# board_PMA.net
KiCad netlist of a schematic drawn in EAGLE
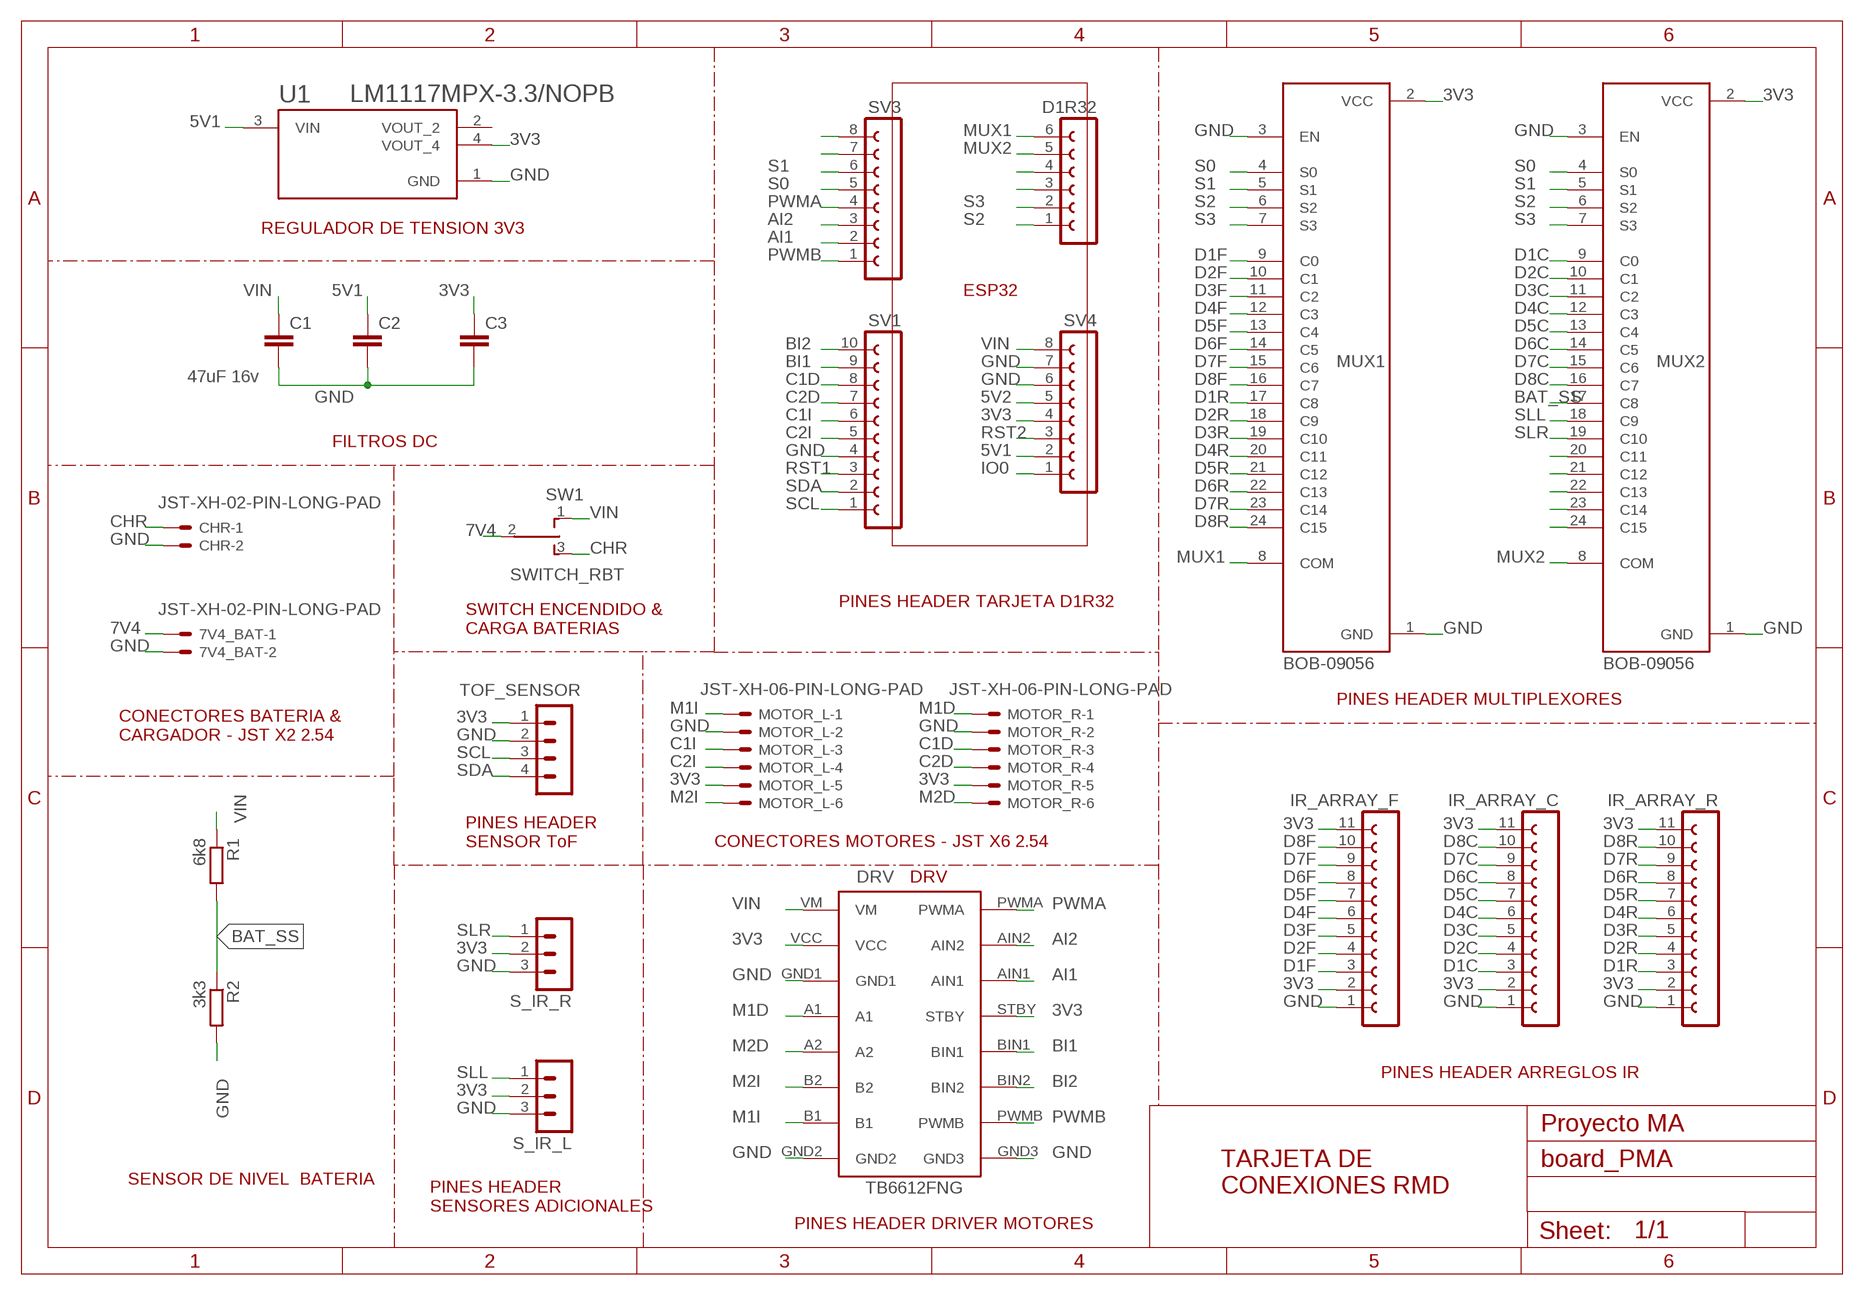
[diagram p0: schematic, sheet 1]

(export (version "E")
  (design (tool "Eeschema 10.0.6"))
  (components
    (comp (ref "7V4_BAT")
      (value "JST-XH-02-PIN-LONG-PAD")
      (footprint "eagle-import:JST-XH-02-PACKAGE-LONG-PAD")
      (libsource (lib "eagle-import") (part "JST-XH-02-PIN-LONG-PAD"))
    )
    (comp (ref "C1")
      (value "47uF 16v")
      (footprint "eagle-import:C1206K")
      (libsource (lib "eagle-import") (part "C-EUC1206K"))
    )
    (comp (ref "C2")
      (value "C-EUC1206K")
      (footprint "eagle-import:C1206K")
      (libsource (lib "eagle-import") (part "C-EUC1206K"))
    )
    (comp (ref "C3")
      (value "C-EUC1206K")
      (footprint "eagle-import:C1206K")
      (libsource (lib "eagle-import") (part "C-EUC1206K"))
    )
    (comp (ref "CHR")
      (value "JST-XH-02-PIN-LONG-PAD")
      (footprint "eagle-import:JST-XH-02-PACKAGE-LONG-PAD")
      (libsource (lib "eagle-import") (part "JST-XH-02-PIN-LONG-PAD"))
    )
    (comp (ref "D1R32")
      (value "FE06-1")
      (footprint "eagle-import:FE06")
      (libsource (lib "eagle-import") (part "FE06-1"))
    )
    (comp (ref "DRV")
      (value "TB6612FNG")
      (footprint "eagle-import:TB6612FNG")
      (libsource (lib "eagle-import") (part "TB6612FNG"))
    )
    (comp (ref "IR_ARRAY_C")
      (value "FE11-1")
      (footprint "eagle-import:FE11")
      (libsource (lib "eagle-import") (part "FE11-1"))
    )
    (comp (ref "IR_ARRAY_F")
      (value "FE11-1")
      (footprint "eagle-import:FE11")
      (libsource (lib "eagle-import") (part "FE11-1"))
    )
    (comp (ref "IR_ARRAY_R")
      (value "FE11-1")
      (footprint "eagle-import:FE11")
      (libsource (lib "eagle-import") (part "FE11-1"))
    )
    (comp (ref "MOTOR_L")
      (value "JST-XH-06-PIN-LONG-PAD")
      (footprint "eagle-import:JST-XH-06-PACKAGE-LONG-PAD")
      (libsource (lib "eagle-import") (part "JST-XH-06-PIN-LONG-PAD"))
    )
    (comp (ref "MOTOR_R")
      (value "JST-XH-06-PIN-LONG-PAD")
      (footprint "eagle-import:JST-XH-06-PACKAGE-LONG-PAD")
      (libsource (lib "eagle-import") (part "JST-XH-06-PIN-LONG-PAD"))
    )
    (comp (ref "MUX1")
      (value "BOB-09056")
      (footprint "eagle-import:XDCR_BOB-09056")
      (fields (field (name "MF") "SparkFun Electronics"))
      (libsource (lib "eagle-import") (part "BOB-09056"))
    )
    (comp (ref "MUX2")
      (value "BOB-09056")
      (footprint "eagle-import:XDCR_BOB-09056")
      (fields (field (name "MF") "SparkFun Electronics"))
      (libsource (lib "eagle-import") (part "BOB-09056"))
    )
    (comp (ref "R1")
      (value "6k8")
      (footprint "eagle-import:0207_10")
      (libsource (lib "eagle-import") (part "R-EU_0207/10"))
    )
    (comp (ref "R2")
      (value "3k3")
      (footprint "eagle-import:0207_10")
      (libsource (lib "eagle-import") (part "R-EU_0207/10"))
    )
    (comp (ref "SV1")
      (value "FE10-1")
      (footprint "eagle-import:FE10")
      (libsource (lib "eagle-import") (part "FE10-1"))
    )
    (comp (ref "SV3")
      (value "FE08-1")
      (footprint "eagle-import:FE08")
      (libsource (lib "eagle-import") (part "FE08-1"))
    )
    (comp (ref "SV4")
      (value "FE08-1")
      (footprint "eagle-import:FE08")
      (libsource (lib "eagle-import") (part "FE08-1"))
    )
    (comp (ref "SW1")
      (value "SWITCH_RBT")
      (footprint "eagle-import:SW")
      (libsource (lib "eagle-import") (part "SWITCH_RBT"))
    )
    (comp (ref "S_IR_L")
      (value "MA03-1")
      (footprint "eagle-import:MA03-1")
      (libsource (lib "eagle-import") (part "MA03-1"))
    )
    (comp (ref "S_IR_R")
      (value "MA03-1")
      (footprint "eagle-import:MA03-1")
      (libsource (lib "eagle-import") (part "MA03-1"))
    )
    (comp (ref "TOF_SENSOR")
      (value "MA04-1")
      (footprint "eagle-import:MA04-1")
      (libsource (lib "eagle-import") (part "MA04-1"))
    )
    (comp (ref "U1")
      (value "LM1117MPX-3.3/NOPB")
      (footprint "eagle-import:VREG_LM1117MPX-3.3_NOPB")
      (fields (field (name "MF") "Texas Instruments"))
      (libsource (lib "eagle-import") (part "LM1117MPX-3.3/NOPB"))
    )
  )
  (nets
    (net (code "1") (name "/3V3") (class "Default")
      (node (ref "C3") (pin "1") (pinfunction "1_1") (pintype "passive"))
      (node (ref "DRV") (pin "STBY") (pinfunction "STBY_STBY") (pintype "bidirectional"))
      (node (ref "DRV") (pin "VCC") (pinfunction "VCC_VCC") (pintype "bidirectional"))
      (node (ref "IR_ARRAY_C") (pin "11") (pinfunction "11_11") (pintype "passive"))
      (node (ref "IR_ARRAY_C") (pin "2") (pinfunction "2_2") (pintype "passive"))
      (node (ref "IR_ARRAY_F") (pin "11") (pinfunction "11_11") (pintype "passive"))
      (node (ref "IR_ARRAY_F") (pin "2") (pinfunction "2_2") (pintype "passive"))
      (node (ref "IR_ARRAY_R") (pin "11") (pinfunction "11_11") (pintype "passive"))
      (node (ref "IR_ARRAY_R") (pin "2") (pinfunction "2_2") (pintype "passive"))
      (node (ref "MOTOR_L") (pin "5") (pinfunction "S_5") (pintype "passive"))
      (node (ref "MOTOR_R") (pin "5") (pinfunction "S_5") (pintype "passive"))
      (node (ref "MUX1") (pin "2") (pinfunction "VCC_2") (pintype "power_in"))
      (node (ref "MUX2") (pin "2") (pinfunction "VCC_2") (pintype "power_in"))
      (node (ref "SV4") (pin "4") (pinfunction "4_4") (pintype "passive"))
      (node (ref "S_IR_L") (pin "2") (pinfunction "2_2") (pintype "passive"))
      (node (ref "S_IR_R") (pin "2") (pinfunction "2_2") (pintype "passive"))
      (node (ref "TOF_SENSOR") (pin "1") (pinfunction "1_1") (pintype "passive"))
      (node (ref "U1") (pin "4") (pinfunction "VOUT_4_4") (pintype "output"))
    )
    (net (code "2") (name "/5V1") (class "Default")
      (node (ref "C2") (pin "1") (pinfunction "1_1") (pintype "passive"))
      (node (ref "SV4") (pin "2") (pinfunction "2_2") (pintype "passive"))
      (node (ref "U1") (pin "3") (pinfunction "VIN_3") (pintype "input"))
    )
    (net (code "3") (name "/5V2") (class "Default")
      (node (ref "SV4") (pin "5") (pinfunction "5_5") (pintype "passive"))
    )
    (net (code "4") (name "/7V4") (class "Default")
      (node (ref "7V4_BAT") (pin "1") (pinfunction "S_1") (pintype "passive"))
      (node (ref "SW1") (pin "2") (pinfunction "2_2") (pintype "passive"))
    )
    (net (code "5") (name "/AI1") (class "Default")
      (node (ref "DRV") (pin "AIN1") (pinfunction "AIN1_AIN1") (pintype "bidirectional"))
      (node (ref "SV3") (pin "2") (pinfunction "2_2") (pintype "passive"))
    )
    (net (code "6") (name "/AI2") (class "Default")
      (node (ref "DRV") (pin "AIN2") (pinfunction "AIN2_AIN2") (pintype "bidirectional"))
      (node (ref "SV3") (pin "3") (pinfunction "3_3") (pintype "passive"))
    )
    (net (code "7") (name "/BI1") (class "Default")
      (node (ref "DRV") (pin "BIN1") (pinfunction "BIN1_BIN1") (pintype "bidirectional"))
      (node (ref "SV1") (pin "9") (pinfunction "9_9") (pintype "passive"))
    )
    (net (code "8") (name "/BI2") (class "Default")
      (node (ref "DRV") (pin "BIN2") (pinfunction "BIN2_BIN2") (pintype "bidirectional"))
      (node (ref "SV1") (pin "10") (pinfunction "10_10") (pintype "passive"))
    )
    (net (code "9") (name "/C1D") (class "Default")
      (node (ref "MOTOR_R") (pin "3") (pinfunction "S_3") (pintype "passive"))
      (node (ref "SV1") (pin "8") (pinfunction "8_8") (pintype "passive"))
    )
    (net (code "10") (name "/C1I") (class "Default")
      (node (ref "MOTOR_L") (pin "3") (pinfunction "S_3") (pintype "passive"))
      (node (ref "SV1") (pin "6") (pinfunction "6_6") (pintype "passive"))
    )
    (net (code "11") (name "/C2D") (class "Default")
      (node (ref "MOTOR_R") (pin "4") (pinfunction "S_4") (pintype "passive"))
      (node (ref "SV1") (pin "7") (pinfunction "7_7") (pintype "passive"))
    )
    (net (code "12") (name "/C2I") (class "Default")
      (node (ref "MOTOR_L") (pin "4") (pinfunction "S_4") (pintype "passive"))
      (node (ref "SV1") (pin "5") (pinfunction "5_5") (pintype "passive"))
    )
    (net (code "13") (name "/CHR") (class "Default")
      (node (ref "CHR") (pin "1") (pinfunction "S_1") (pintype "passive"))
      (node (ref "SW1") (pin "3") (pinfunction "3_3") (pintype "passive"))
    )
    (net (code "14") (name "/D1C") (class "Default")
      (node (ref "IR_ARRAY_C") (pin "3") (pinfunction "3_3") (pintype "passive"))
      (node (ref "MUX2") (pin "9") (pinfunction "C0_9") (pintype "input"))
    )
    (net (code "15") (name "/D1F") (class "Default")
      (node (ref "IR_ARRAY_F") (pin "3") (pinfunction "3_3") (pintype "passive"))
      (node (ref "MUX1") (pin "9") (pinfunction "C0_9") (pintype "input"))
    )
    (net (code "16") (name "/D1R") (class "Default")
      (node (ref "IR_ARRAY_R") (pin "3") (pinfunction "3_3") (pintype "passive"))
      (node (ref "MUX1") (pin "17") (pinfunction "C8_17") (pintype "input"))
    )
    (net (code "17") (name "/D2C") (class "Default")
      (node (ref "IR_ARRAY_C") (pin "4") (pinfunction "4_4") (pintype "passive"))
      (node (ref "MUX2") (pin "10") (pinfunction "C1_10") (pintype "input"))
    )
    (net (code "18") (name "/D2F") (class "Default")
      (node (ref "IR_ARRAY_F") (pin "4") (pinfunction "4_4") (pintype "passive"))
      (node (ref "MUX1") (pin "10") (pinfunction "C1_10") (pintype "input"))
    )
    (net (code "19") (name "/D2R") (class "Default")
      (node (ref "IR_ARRAY_R") (pin "4") (pinfunction "4_4") (pintype "passive"))
      (node (ref "MUX1") (pin "18") (pinfunction "C9_18") (pintype "input"))
    )
    (net (code "20") (name "/D3C") (class "Default")
      (node (ref "IR_ARRAY_C") (pin "5") (pinfunction "5_5") (pintype "passive"))
      (node (ref "MUX2") (pin "11") (pinfunction "C2_11") (pintype "input"))
    )
    (net (code "21") (name "/D3F") (class "Default")
      (node (ref "IR_ARRAY_F") (pin "5") (pinfunction "5_5") (pintype "passive"))
      (node (ref "MUX1") (pin "11") (pinfunction "C2_11") (pintype "input"))
    )
    (net (code "22") (name "/D3R") (class "Default")
      (node (ref "IR_ARRAY_R") (pin "5") (pinfunction "5_5") (pintype "passive"))
      (node (ref "MUX1") (pin "19") (pinfunction "C10_19") (pintype "input"))
    )
    (net (code "23") (name "/D4C") (class "Default")
      (node (ref "IR_ARRAY_C") (pin "6") (pinfunction "6_6") (pintype "passive"))
      (node (ref "MUX2") (pin "12") (pinfunction "C3_12") (pintype "input"))
    )
    (net (code "24") (name "/D4F") (class "Default")
      (node (ref "IR_ARRAY_F") (pin "6") (pinfunction "6_6") (pintype "passive"))
      (node (ref "MUX1") (pin "12") (pinfunction "C3_12") (pintype "input"))
    )
    (net (code "25") (name "/D4R") (class "Default")
      (node (ref "IR_ARRAY_R") (pin "6") (pinfunction "6_6") (pintype "passive"))
      (node (ref "MUX1") (pin "20") (pinfunction "C11_20") (pintype "input"))
    )
    (net (code "26") (name "/D5C") (class "Default")
      (node (ref "IR_ARRAY_C") (pin "7") (pinfunction "7_7") (pintype "passive"))
      (node (ref "MUX2") (pin "13") (pinfunction "C4_13") (pintype "input"))
    )
    (net (code "27") (name "/D5F") (class "Default")
      (node (ref "IR_ARRAY_F") (pin "7") (pinfunction "7_7") (pintype "passive"))
      (node (ref "MUX1") (pin "13") (pinfunction "C4_13") (pintype "input"))
    )
    (net (code "28") (name "/D5R") (class "Default")
      (node (ref "IR_ARRAY_R") (pin "7") (pinfunction "7_7") (pintype "passive"))
      (node (ref "MUX1") (pin "21") (pinfunction "C12_21") (pintype "input"))
    )
    (net (code "29") (name "/D6C") (class "Default")
      (node (ref "IR_ARRAY_C") (pin "8") (pinfunction "8_8") (pintype "passive"))
      (node (ref "MUX2") (pin "14") (pinfunction "C5_14") (pintype "input"))
    )
    (net (code "30") (name "/D6F") (class "Default")
      (node (ref "IR_ARRAY_F") (pin "8") (pinfunction "8_8") (pintype "passive"))
      (node (ref "MUX1") (pin "14") (pinfunction "C5_14") (pintype "input"))
    )
    (net (code "31") (name "/D6R") (class "Default")
      (node (ref "IR_ARRAY_R") (pin "8") (pinfunction "8_8") (pintype "passive"))
      (node (ref "MUX1") (pin "22") (pinfunction "C13_22") (pintype "input"))
    )
    (net (code "32") (name "/D7C") (class "Default")
      (node (ref "IR_ARRAY_C") (pin "9") (pinfunction "9_9") (pintype "passive"))
      (node (ref "MUX2") (pin "15") (pinfunction "C6_15") (pintype "input"))
    )
    (net (code "33") (name "/D7F") (class "Default")
      (node (ref "IR_ARRAY_F") (pin "9") (pinfunction "9_9") (pintype "passive"))
      (node (ref "MUX1") (pin "15") (pinfunction "C6_15") (pintype "input"))
    )
    (net (code "34") (name "/D7R") (class "Default")
      (node (ref "IR_ARRAY_R") (pin "9") (pinfunction "9_9") (pintype "passive"))
      (node (ref "MUX1") (pin "23") (pinfunction "C14_23") (pintype "input"))
    )
    (net (code "35") (name "/D8C") (class "Default")
      (node (ref "IR_ARRAY_C") (pin "10") (pinfunction "10_10") (pintype "passive"))
      (node (ref "MUX2") (pin "16") (pinfunction "C7_16") (pintype "input"))
    )
    (net (code "36") (name "/D8F") (class "Default")
      (node (ref "IR_ARRAY_F") (pin "10") (pinfunction "10_10") (pintype "passive"))
      (node (ref "MUX1") (pin "16") (pinfunction "C7_16") (pintype "input"))
    )
    (net (code "37") (name "/D8R") (class "Default")
      (node (ref "IR_ARRAY_R") (pin "10") (pinfunction "10_10") (pintype "passive"))
      (node (ref "MUX1") (pin "24") (pinfunction "C15_24") (pintype "input"))
    )
    (net (code "38") (name "/GND") (class "Default")
      (node (ref "7V4_BAT") (pin "2") (pinfunction "S_2") (pintype "passive"))
      (node (ref "C1") (pin "2") (pinfunction "2_2") (pintype "passive"))
      (node (ref "C2") (pin "2") (pinfunction "2_2") (pintype "passive"))
      (node (ref "C3") (pin "2") (pinfunction "2_2") (pintype "passive"))
      (node (ref "CHR") (pin "2") (pinfunction "S_2") (pintype "passive"))
      (node (ref "DRV") (pin "GND1") (pinfunction "GND1_GND1") (pintype "bidirectional"))
      (node (ref "DRV") (pin "GND2") (pinfunction "GND2_GND2") (pintype "bidirectional"))
      (node (ref "DRV") (pin "GND3") (pinfunction "GND3_GND3") (pintype "bidirectional"))
      (node (ref "IR_ARRAY_C") (pin "1") (pinfunction "1_1") (pintype "passive"))
      (node (ref "IR_ARRAY_F") (pin "1") (pinfunction "1_1") (pintype "passive"))
      (node (ref "IR_ARRAY_R") (pin "1") (pinfunction "1_1") (pintype "passive"))
      (node (ref "MOTOR_L") (pin "2") (pinfunction "S_2") (pintype "passive"))
      (node (ref "MOTOR_R") (pin "2") (pinfunction "S_2") (pintype "passive"))
      (node (ref "MUX1") (pin "1") (pinfunction "GND_1") (pintype "power_in"))
      (node (ref "MUX1") (pin "3") (pinfunction "EN_3") (pintype "input"))
      (node (ref "MUX2") (pin "1") (pinfunction "GND_1") (pintype "power_in"))
      (node (ref "MUX2") (pin "3") (pinfunction "EN_3") (pintype "input"))
      (node (ref "R2") (pin "2") (pinfunction "2_2") (pintype "passive"))
      (node (ref "SV1") (pin "4") (pinfunction "4_4") (pintype "passive"))
      (node (ref "SV4") (pin "6") (pinfunction "6_6") (pintype "passive"))
      (node (ref "SV4") (pin "7") (pinfunction "7_7") (pintype "passive"))
      (node (ref "S_IR_L") (pin "3") (pinfunction "3_3") (pintype "passive"))
      (node (ref "S_IR_R") (pin "3") (pinfunction "3_3") (pintype "passive"))
      (node (ref "TOF_SENSOR") (pin "2") (pinfunction "2_2") (pintype "passive"))
      (node (ref "U1") (pin "1") (pinfunction "GND_1") (pintype "power_in"))
    )
    (net (code "39") (name "/IO0") (class "Default")
      (node (ref "SV4") (pin "1") (pinfunction "1_1") (pintype "passive"))
    )
    (net (code "40") (name "/M1D") (class "Default")
      (node (ref "DRV") (pin "A1") (pinfunction "A1_A1") (pintype "bidirectional"))
      (node (ref "MOTOR_R") (pin "1") (pinfunction "S_1") (pintype "passive"))
    )
    (net (code "41") (name "/M1I") (class "Default")
      (node (ref "DRV") (pin "B1") (pinfunction "B1_B1") (pintype "bidirectional"))
      (node (ref "MOTOR_L") (pin "1") (pinfunction "S_1") (pintype "passive"))
    )
    (net (code "42") (name "/M2D") (class "Default")
      (node (ref "DRV") (pin "A2") (pinfunction "A2_A2") (pintype "bidirectional"))
      (node (ref "MOTOR_R") (pin "6") (pinfunction "S_6") (pintype "passive"))
    )
    (net (code "43") (name "/M2I") (class "Default")
      (node (ref "DRV") (pin "B2") (pinfunction "B2_B2") (pintype "bidirectional"))
      (node (ref "MOTOR_L") (pin "6") (pinfunction "S_6") (pintype "passive"))
    )
    (net (code "44") (name "/MUX1") (class "Default")
      (node (ref "D1R32") (pin "6") (pinfunction "6_6") (pintype "passive"))
      (node (ref "MUX1") (pin "8") (pinfunction "COM_8") (pintype "bidirectional"))
    )
    (net (code "45") (name "/MUX2") (class "Default")
      (node (ref "D1R32") (pin "5") (pinfunction "5_5") (pintype "passive"))
      (node (ref "MUX2") (pin "8") (pinfunction "COM_8") (pintype "bidirectional"))
    )
    (net (code "46") (name "/PWMA") (class "Default")
      (node (ref "DRV") (pin "PWMA") (pinfunction "PWMA_PWMA") (pintype "bidirectional"))
      (node (ref "SV3") (pin "4") (pinfunction "4_4") (pintype "passive"))
    )
    (net (code "47") (name "/PWMB") (class "Default")
      (node (ref "DRV") (pin "PWMB") (pinfunction "PWMB_PWMB") (pintype "bidirectional"))
      (node (ref "SV3") (pin "1") (pinfunction "1_1") (pintype "passive"))
    )
    (net (code "48") (name "/RST1") (class "Default")
      (node (ref "SV1") (pin "3") (pinfunction "3_3") (pintype "passive"))
    )
    (net (code "49") (name "/RST2") (class "Default")
      (node (ref "SV4") (pin "3") (pinfunction "3_3") (pintype "passive"))
    )
    (net (code "50") (name "/S0") (class "Default")
      (node (ref "MUX1") (pin "4") (pinfunction "S0_4") (pintype "input"))
      (node (ref "MUX2") (pin "4") (pinfunction "S0_4") (pintype "input"))
      (node (ref "SV3") (pin "5") (pinfunction "5_5") (pintype "passive"))
    )
    (net (code "51") (name "/S1") (class "Default")
      (node (ref "MUX1") (pin "5") (pinfunction "S1_5") (pintype "input"))
      (node (ref "MUX2") (pin "5") (pinfunction "S1_5") (pintype "input"))
      (node (ref "SV3") (pin "6") (pinfunction "6_6") (pintype "passive"))
    )
    (net (code "52") (name "/S2") (class "Default")
      (node (ref "D1R32") (pin "1") (pinfunction "1_1") (pintype "passive"))
      (node (ref "MUX1") (pin "6") (pinfunction "S2_6") (pintype "input"))
      (node (ref "MUX2") (pin "6") (pinfunction "S2_6") (pintype "input"))
    )
    (net (code "53") (name "/S3") (class "Default")
      (node (ref "D1R32") (pin "2") (pinfunction "2_2") (pintype "passive"))
      (node (ref "MUX1") (pin "7") (pinfunction "S3_7") (pintype "input"))
      (node (ref "MUX2") (pin "7") (pinfunction "S3_7") (pintype "input"))
    )
    (net (code "54") (name "/SCL") (class "Default")
      (node (ref "SV1") (pin "1") (pinfunction "1_1") (pintype "passive"))
      (node (ref "TOF_SENSOR") (pin "3") (pinfunction "3_3") (pintype "passive"))
    )
    (net (code "55") (name "/SDA") (class "Default")
      (node (ref "SV1") (pin "2") (pinfunction "2_2") (pintype "passive"))
      (node (ref "TOF_SENSOR") (pin "4") (pinfunction "4_4") (pintype "passive"))
    )
    (net (code "56") (name "/SLL") (class "Default")
      (node (ref "MUX2") (pin "18") (pinfunction "C9_18") (pintype "input"))
      (node (ref "S_IR_L") (pin "1") (pinfunction "1_1") (pintype "passive"))
    )
    (net (code "57") (name "/SLR") (class "Default")
      (node (ref "MUX2") (pin "19") (pinfunction "C10_19") (pintype "input"))
      (node (ref "S_IR_R") (pin "1") (pinfunction "1_1") (pintype "passive"))
    )
    (net (code "58") (name "/VIN") (class "Default")
      (node (ref "C1") (pin "1") (pinfunction "1_1") (pintype "passive"))
      (node (ref "DRV") (pin "VM") (pinfunction "VM_VM") (pintype "bidirectional"))
      (node (ref "R1") (pin "1") (pinfunction "1_1") (pintype "passive"))
      (node (ref "SV4") (pin "8") (pinfunction "8_8") (pintype "passive"))
      (node (ref "SW1") (pin "1") (pinfunction "1_1") (pintype "passive"))
    )
    (net (code "59") (name "BAT_SS") (class "Default")
      (node (ref "MUX2") (pin "17") (pinfunction "C8_17") (pintype "input"))
      (node (ref "R1") (pin "2") (pinfunction "2_2") (pintype "passive"))
      (node (ref "R2") (pin "1") (pinfunction "1_1") (pintype "passive"))
    )
    (net (code "60") (name "unconnected-(D1R32-Pad3)") (class "Default")
      (node (ref "D1R32") (pin "3") (pinfunction "3_3") (pintype "passive"))
    )
    (net (code "61") (name "unconnected-(D1R32-Pad4)") (class "Default")
      (node (ref "D1R32") (pin "4") (pinfunction "4_4") (pintype "passive"))
    )
    (net (code "62") (name "unconnected-(MUX2-C11-Pad20)") (class "Default")
      (node (ref "MUX2") (pin "20") (pinfunction "C11_20") (pintype "input"))
    )
    (net (code "63") (name "unconnected-(MUX2-C12-Pad21)") (class "Default")
      (node (ref "MUX2") (pin "21") (pinfunction "C12_21") (pintype "input"))
    )
    (net (code "64") (name "unconnected-(MUX2-C13-Pad22)") (class "Default")
      (node (ref "MUX2") (pin "22") (pinfunction "C13_22") (pintype "input"))
    )
    (net (code "65") (name "unconnected-(MUX2-C14-Pad23)") (class "Default")
      (node (ref "MUX2") (pin "23") (pinfunction "C14_23") (pintype "input"))
    )
    (net (code "66") (name "unconnected-(MUX2-C15-Pad24)") (class "Default")
      (node (ref "MUX2") (pin "24") (pinfunction "C15_24") (pintype "input"))
    )
    (net (code "67") (name "unconnected-(SV3-Pad7)") (class "Default")
      (node (ref "SV3") (pin "7") (pinfunction "7_7") (pintype "passive"))
    )
    (net (code "68") (name "unconnected-(SV3-Pad8)") (class "Default")
      (node (ref "SV3") (pin "8") (pinfunction "8_8") (pintype "passive"))
    )
    (net (code "69") (name "unconnected-(U1-VOUT_2-Pad2)") (class "Default")
      (node (ref "U1") (pin "2") (pinfunction "VOUT_2_2") (pintype "output"))
    )
  )
)
